# schema.net
KiCad netlist of a schematic drawn in EAGLE
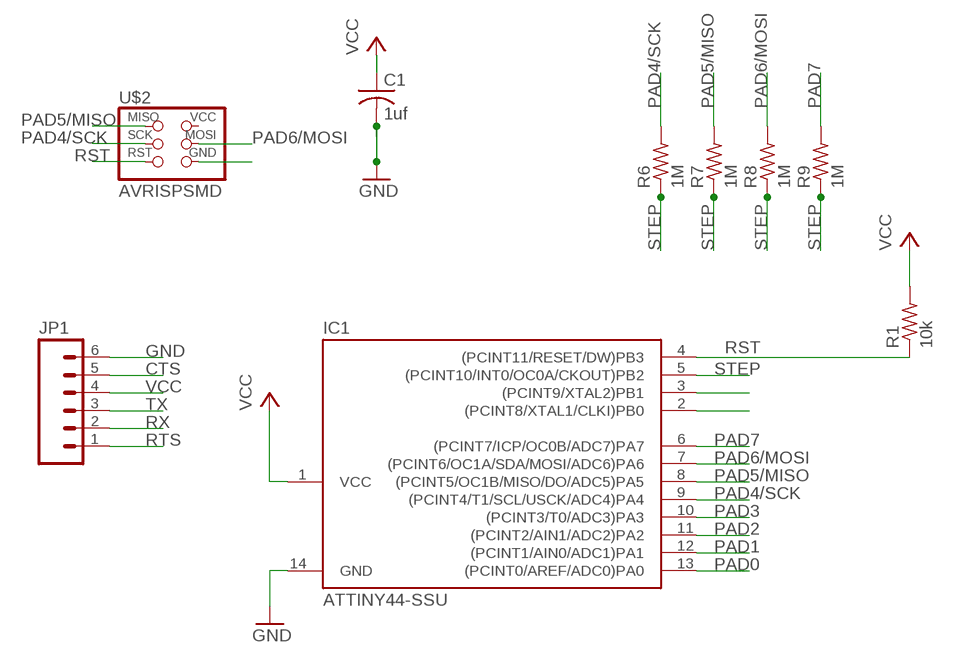
[diagram p0: schematic, sheet 1]

(export (version "E")
  (design (tool "Eeschema 10.0.6"))
  (components
    (comp (ref "C1")
      (value "1uf")
      (footprint "eagle-import:C1206")
      (libsource (lib "eagle-import") (part "C-USC1206"))
    )
    (comp (ref "IC1")
      (value "ATTINY44-SSU")
      (footprint "eagle-import:SOIC14")
      (libsource (lib "eagle-import") (part "ATTINY44-SSU"))
    )
    (comp (ref "JP1")
      (value "M06SMD")
      (footprint "eagle-import:1X06-SMD")
      (libsource (lib "eagle-import") (part "M06SMD"))
    )
    (comp (ref "R1")
      (value "10k")
      (footprint "eagle-import:R1206")
      (libsource (lib "eagle-import") (part "R-US_R1206"))
    )
    (comp (ref "R6")
      (value "1M")
      (footprint "eagle-import:1206")
      (libsource (lib "eagle-import") (part "RESISTOR1206"))
    )
    (comp (ref "R7")
      (value "1M")
      (footprint "eagle-import:1206")
      (libsource (lib "eagle-import") (part "RESISTOR1206"))
    )
    (comp (ref "R8")
      (value "1M")
      (footprint "eagle-import:1206")
      (libsource (lib "eagle-import") (part "RESISTOR1206"))
    )
    (comp (ref "R9")
      (value "1M")
      (footprint "eagle-import:1206")
      (libsource (lib "eagle-import") (part "RESISTOR1206"))
    )
    (comp (ref "U$2")
      (value "AVRISPSMD")
      (footprint "eagle-import:2X03SMD")
      (libsource (lib "eagle-import") (part "AVRISPSMD"))
    )
  )
  (nets
    (net (code "1") (name "/CTS") (class "Default")
      (node (ref "JP1") (pin "5") (pinfunction "5_5") (pintype "passive"))
    )
    (net (code "2") (name "/PAD0") (class "Default")
      (node (ref "IC1") (pin "13") (pinfunction "(PCINT0/AREF/ADC0)PA0_13") (pintype "bidirectional"))
    )
    (net (code "3") (name "/PAD1") (class "Default")
      (node (ref "IC1") (pin "12") (pinfunction "(PCINT1/AIN0/ADC1)PA1_12") (pintype "bidirectional"))
    )
    (net (code "4") (name "/PAD2") (class "Default")
      (node (ref "IC1") (pin "11") (pinfunction "(PCINT2/AIN1/ADC2)PA2_11") (pintype "bidirectional"))
    )
    (net (code "5") (name "/PAD3") (class "Default")
      (node (ref "IC1") (pin "10") (pinfunction "(PCINT3/T0/ADC3)PA3_10") (pintype "bidirectional"))
    )
    (net (code "6") (name "/PAD4{slash}SCK") (class "Default")
      (node (ref "IC1") (pin "9") (pinfunction "(PCINT4/T1/SCL/USCK/ADC4)PA4_9") (pintype "bidirectional"))
      (node (ref "R6") (pin "2") (pinfunction "2_2") (pintype "passive"))
      (node (ref "U$2") (pin "3") (pinfunction "SCK_3") (pintype "passive"))
    )
    (net (code "7") (name "/PAD5{slash}MISO") (class "Default")
      (node (ref "IC1") (pin "8") (pinfunction "(PCINT5/OC1B/MISO/DO/ADC5)PA5_8") (pintype "bidirectional"))
      (node (ref "R7") (pin "2") (pinfunction "2_2") (pintype "passive"))
      (node (ref "U$2") (pin "1") (pinfunction "MISO_1") (pintype "passive"))
    )
    (net (code "8") (name "/PAD6{slash}MOSI") (class "Default")
      (node (ref "IC1") (pin "7") (pinfunction "(PCINT6/OC1A/SDA/MOSI/ADC6)PA6_7") (pintype "bidirectional"))
      (node (ref "R8") (pin "2") (pinfunction "2_2") (pintype "passive"))
      (node (ref "U$2") (pin "4") (pinfunction "MOSI_4") (pintype "passive"))
    )
    (net (code "9") (name "/PAD7") (class "Default")
      (node (ref "IC1") (pin "6") (pinfunction "(PCINT7/ICP/OC0B/ADC7)PA7_6") (pintype "bidirectional"))
      (node (ref "R9") (pin "2") (pinfunction "2_2") (pintype "passive"))
    )
    (net (code "10") (name "/RST") (class "Default")
      (node (ref "IC1") (pin "4") (pinfunction "(PCINT11/RESET/DW)PB3_4") (pintype "bidirectional"))
      (node (ref "R1") (pin "1") (pinfunction "1_1") (pintype "passive"))
      (node (ref "U$2") (pin "5") (pinfunction "RST_5") (pintype "passive"))
    )
    (net (code "11") (name "/RTS") (class "Default")
      (node (ref "JP1") (pin "1") (pinfunction "1_1") (pintype "passive"))
    )
    (net (code "12") (name "/RX") (class "Default")
      (node (ref "IC1") (pin "2") (pinfunction "(PCINT8/XTAL1/CLKI)PB0_2") (pintype "bidirectional"))
      (node (ref "JP1") (pin "2") (pinfunction "2_2") (pintype "passive"))
    )
    (net (code "13") (name "/STEP") (class "Default")
      (node (ref "IC1") (pin "5") (pinfunction "(PCINT10/INT0/OC0A/CKOUT)PB2_5") (pintype "bidirectional"))
      (node (ref "R6") (pin "1") (pinfunction "1_1") (pintype "passive"))
      (node (ref "R7") (pin "1") (pinfunction "1_1") (pintype "passive"))
      (node (ref "R8") (pin "1") (pinfunction "1_1") (pintype "passive"))
      (node (ref "R9") (pin "1") (pinfunction "1_1") (pintype "passive"))
    )
    (net (code "14") (name "/TX") (class "Default")
      (node (ref "IC1") (pin "3") (pinfunction "(PCINT9/XTAL2)PB1_3") (pintype "bidirectional"))
      (node (ref "JP1") (pin "3") (pinfunction "3_3") (pintype "passive"))
    )
    (net (code "15") (name "GND") (class "Default")
      (node (ref "C1") (pin "2") (pinfunction "2_2") (pintype "passive"))
      (node (ref "IC1") (pin "14") (pinfunction "GND_14") (pintype "power_in"))
      (node (ref "JP1") (pin "6") (pinfunction "6_6") (pintype "passive"))
      (node (ref "U$2") (pin "6") (pinfunction "GND_6") (pintype "passive"))
    )
    (net (code "16") (name "VCC") (class "Default")
      (node (ref "C1") (pin "1") (pinfunction "1_1") (pintype "passive"))
      (node (ref "IC1") (pin "1") (pinfunction "VCC_1") (pintype "power_in"))
      (node (ref "JP1") (pin "4") (pinfunction "4_4") (pintype "passive"))
      (node (ref "R1") (pin "2") (pinfunction "2_2") (pintype "passive"))
    )
    (net (code "17") (name "unconnected-(U$2-VCC-Pad2)") (class "Default")
      (node (ref "U$2") (pin "2") (pinfunction "VCC_2") (pintype "passive"))
    )
  )
)
